# Button_PCBA.net
KiCad netlist of a schematic drawn in EAGLE
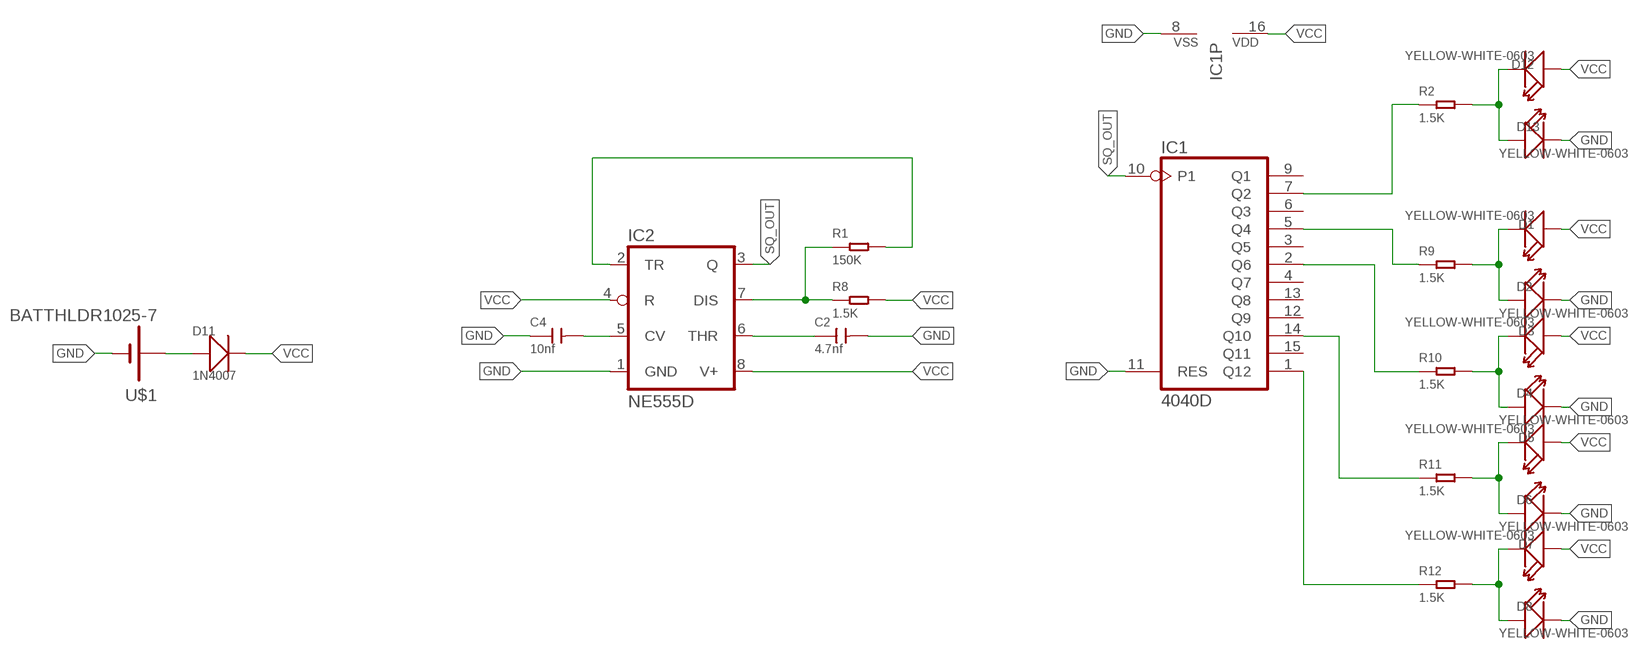
[diagram p0: schematic, sheet 1]

(export (version "E")
  (design (tool "Eeschema 10.0.6"))
  (components
    (comp (ref "C2")
      (value "4.7nf")
      (footprint "eagle-import:C0603")
      (fields (field (name "MPN") "CC0603KRX7R9BB472"))
      (libsource (lib "eagle-import") (part "CERAMIC-4.7NF-50V-10%-X7R(0603)"))
    )
    (comp (ref "C4")
      (value "10nf")
      (footprint "eagle-import:C0603")
      (fields (field (name "MPN") "CC0603KRX7R9BB103"))
      (libsource (lib "eagle-import") (part "CERAMIC-10NF-50V-10%-X7R(0603)"))
    )
    (comp (ref "D1")
      (value "YELLOW-WHITE-0603")
      (footprint "eagle-import:LED-0603")
      (fields (field (name "MPN") "ADL-0603W"))
      (libsource (lib "eagle-import") (part "SMD-LED-YELLOW-WHITE(0603)"))
    )
    (comp (ref "D2")
      (value "YELLOW-WHITE-0603")
      (footprint "eagle-import:LED-0603")
      (fields (field (name "MPN") "ADL-0603W"))
      (libsource (lib "eagle-import") (part "SMD-LED-YELLOW-WHITE(0603)"))
    )
    (comp (ref "D3")
      (value "YELLOW-WHITE-0603")
      (footprint "eagle-import:LED-0603")
      (fields (field (name "MPN") "ADL-0603W"))
      (libsource (lib "eagle-import") (part "SMD-LED-YELLOW-WHITE(0603)"))
    )
    (comp (ref "D4")
      (value "YELLOW-WHITE-0603")
      (footprint "eagle-import:LED-0603")
      (fields (field (name "MPN") "ADL-0603W"))
      (libsource (lib "eagle-import") (part "SMD-LED-YELLOW-WHITE(0603)"))
    )
    (comp (ref "D5")
      (value "YELLOW-WHITE-0603")
      (footprint "eagle-import:LED-0603")
      (fields (field (name "MPN") "ADL-0603W"))
      (libsource (lib "eagle-import") (part "SMD-LED-YELLOW-WHITE(0603)"))
    )
    (comp (ref "D6")
      (value "YELLOW-WHITE-0603")
      (footprint "eagle-import:LED-0603")
      (fields (field (name "MPN") "ADL-0603W"))
      (libsource (lib "eagle-import") (part "SMD-LED-YELLOW-WHITE(0603)"))
    )
    (comp (ref "D7")
      (value "YELLOW-WHITE-0603")
      (footprint "eagle-import:LED-0603")
      (fields (field (name "MPN") "ADL-0603W"))
      (libsource (lib "eagle-import") (part "SMD-LED-YELLOW-WHITE(0603)"))
    )
    (comp (ref "D8")
      (value "YELLOW-WHITE-0603")
      (footprint "eagle-import:LED-0603")
      (fields (field (name "MPN") "ADL-0603W"))
      (libsource (lib "eagle-import") (part "SMD-LED-YELLOW-WHITE(0603)"))
    )
    (comp (ref "D11")
      (value "1N4007")
      (footprint "eagle-import:DO-214AC")
      (libsource (lib "eagle-import") (part "DIODE-GEN-PURPOSE-1KV-1A(DO-214AC)"))
    )
    (comp (ref "D12")
      (value "YELLOW-WHITE-0603")
      (footprint "eagle-import:LED-0603")
      (fields (field (name "MPN") "ADL-0603W"))
      (libsource (lib "eagle-import") (part "SMD-LED-YELLOW-WHITE(0603)"))
    )
    (comp (ref "D13")
      (value "YELLOW-WHITE-0603")
      (footprint "eagle-import:LED-0603")
      (fields (field (name "MPN") "ADL-0603W"))
      (libsource (lib "eagle-import") (part "SMD-LED-YELLOW-WHITE(0603)"))
    )
    (comp (ref "IC1")
      (value "4040D")
      (footprint "eagle-import:SO16")
      (libsource (lib "eagle-import") (part "4040D"))
    )
    (comp (ref "IC2")
      (value "NE555D")
      (footprint "eagle-import:SO08")
      (libsource (lib "eagle-import") (part "555DNE"))
    )
    (comp (ref "R1")
      (value "150K")
      (footprint "eagle-import:R0603")
      (fields (field (name "MPN") "RC0603FR-07150KL"))
      (libsource (lib "eagle-import") (part "SMD-RES-150K-1%-1/10W(0603)"))
    )
    (comp (ref "R2")
      (value "1.5K")
      (footprint "eagle-import:R0603")
      (fields (field (name "MPN") "RC0603FR-071K5L"))
      (libsource (lib "eagle-import") (part "SMD-RES-680R-1%-1/10W(0603)"))
    )
    (comp (ref "R8")
      (value "1.5K")
      (footprint "eagle-import:R0603")
      (fields (field (name "MPN") "RC0603FR-071K5L"))
      (libsource (lib "eagle-import") (part "SMD-RES-4.7K-1%-1/10W(0603)"))
    )
    (comp (ref "R9")
      (value "1.5K")
      (footprint "eagle-import:R0603")
      (fields (field (name "MPN") "RC0603FR-071K5L"))
      (libsource (lib "eagle-import") (part "SMD-RES-680R-1%-1/10W(0603)"))
    )
    (comp (ref "R10")
      (value "1.5K")
      (footprint "eagle-import:R0603")
      (fields (field (name "MPN") "RC0603FR-071K5L"))
      (libsource (lib "eagle-import") (part "SMD-RES-680R-1%-1/10W(0603)"))
    )
    (comp (ref "R11")
      (value "1.5K")
      (footprint "eagle-import:R0603")
      (fields (field (name "MPN") "RC0603FR-071K5L"))
      (libsource (lib "eagle-import") (part "SMD-RES-680R-1%-1/10W(0603)"))
    )
    (comp (ref "R12")
      (value "1.5K")
      (footprint "eagle-import:R0603")
      (fields (field (name "MPN") "RC0603FR-071K5L"))
      (libsource (lib "eagle-import") (part "SMD-RES-680R-1%-1/10W(0603)"))
    )
    (comp (ref "U$1")
      (value "BATTHLDR1025-7")
      (footprint "eagle-import:BATTHLDR1025-7")
      (libsource (lib "eagle-import") (part "BATTHLDR1025-7"))
    )
  )
  (nets
    (net (code "1") (name "GND") (class "Default")
      (node (ref "C2") (pin "2") (pinfunction "2_2") (pintype "passive"))
      (node (ref "C4") (pin "1") (pinfunction "1_1") (pintype "passive"))
      (node (ref "D13") (pin "-") (pinfunction "-_-") (pintype "passive"))
      (node (ref "D2") (pin "-") (pinfunction "-_-") (pintype "passive"))
      (node (ref "D4") (pin "-") (pinfunction "-_-") (pintype "passive"))
      (node (ref "D6") (pin "-") (pinfunction "-_-") (pintype "passive"))
      (node (ref "D8") (pin "-") (pinfunction "-_-") (pintype "passive"))
      (node (ref "IC1") (pin "11") (pinfunction "RES_11") (pintype "input"))
      (node (ref "IC1") (pin "8") (pinfunction "VSS_8") (pintype "power_in"))
      (node (ref "IC2") (pin "1") (pinfunction "GND_1") (pintype "power_in"))
      (node (ref "U$1") (pin "NEGATIVE") (pinfunction "-_NEGATIVE") (pintype "power_in"))
    )
    (net (code "2") (name "Net-(D1-Pad-)") (class "Default")
      (node (ref "D1") (pin "-") (pinfunction "-_-") (pintype "passive"))
      (node (ref "D2") (pin "+") (pinfunction "+_+") (pintype "passive"))
      (node (ref "R9") (pin "2") (pinfunction "2_2") (pintype "passive"))
    )
    (net (code "3") (name "Net-(D3-Pad-)") (class "Default")
      (node (ref "D3") (pin "-") (pinfunction "-_-") (pintype "passive"))
      (node (ref "D4") (pin "+") (pinfunction "+_+") (pintype "passive"))
      (node (ref "R10") (pin "2") (pinfunction "2_2") (pintype "passive"))
    )
    (net (code "4") (name "Net-(D5-Pad-)") (class "Default")
      (node (ref "D5") (pin "-") (pinfunction "-_-") (pintype "passive"))
      (node (ref "D6") (pin "+") (pinfunction "+_+") (pintype "passive"))
      (node (ref "R11") (pin "2") (pinfunction "2_2") (pintype "passive"))
    )
    (net (code "5") (name "Net-(D7-Pad-)") (class "Default")
      (node (ref "D7") (pin "-") (pinfunction "-_-") (pintype "passive"))
      (node (ref "D8") (pin "+") (pinfunction "+_+") (pintype "passive"))
      (node (ref "R12") (pin "2") (pinfunction "2_2") (pintype "passive"))
    )
    (net (code "6") (name "Net-(D11-+)") (class "Default")
      (node (ref "D11") (pin "1") (pinfunction "+_1") (pintype "passive"))
      (node (ref "U$1") (pin "POSITIVE") (pinfunction "+_POSITIVE") (pintype "power_in"))
    )
    (net (code "7") (name "Net-(D12-Pad-)") (class "Default")
      (node (ref "D12") (pin "-") (pinfunction "-_-") (pintype "passive"))
      (node (ref "D13") (pin "+") (pinfunction "+_+") (pintype "passive"))
      (node (ref "R2") (pin "2") (pinfunction "2_2") (pintype "passive"))
    )
    (net (code "8") (name "Net-(IC1A-Q2)") (class "Default")
      (node (ref "IC1") (pin "7") (pinfunction "Q2_7") (pintype "output"))
      (node (ref "R2") (pin "1") (pinfunction "1_1") (pintype "passive"))
    )
    (net (code "9") (name "Net-(IC1A-Q4)") (class "Default")
      (node (ref "IC1") (pin "5") (pinfunction "Q4_5") (pintype "output"))
      (node (ref "R9") (pin "1") (pinfunction "1_1") (pintype "passive"))
    )
    (net (code "10") (name "Net-(IC1A-Q6)") (class "Default")
      (node (ref "IC1") (pin "2") (pinfunction "Q6_2") (pintype "output"))
      (node (ref "R10") (pin "1") (pinfunction "1_1") (pintype "passive"))
    )
    (net (code "11") (name "Net-(IC1A-Q10)") (class "Default")
      (node (ref "IC1") (pin "14") (pinfunction "Q10_14") (pintype "output"))
      (node (ref "R11") (pin "1") (pinfunction "1_1") (pintype "passive"))
    )
    (net (code "12") (name "Net-(IC1A-Q12)") (class "Default")
      (node (ref "IC1") (pin "1") (pinfunction "Q12_1") (pintype "output"))
      (node (ref "R12") (pin "1") (pinfunction "1_1") (pintype "passive"))
    )
    (net (code "13") (name "Net-(IC2-CV)") (class "Default")
      (node (ref "C4") (pin "2") (pinfunction "2_2") (pintype "passive"))
      (node (ref "IC2") (pin "5") (pinfunction "CV_5") (pintype "input"))
    )
    (net (code "14") (name "Net-(IC2-DIS)") (class "Default")
      (node (ref "IC2") (pin "7") (pinfunction "DIS_7") (pintype "input"))
      (node (ref "R1") (pin "1") (pinfunction "1_1") (pintype "passive"))
      (node (ref "R8") (pin "1") (pinfunction "1_1") (pintype "passive"))
    )
    (net (code "15") (name "Net-(IC2-THR)") (class "Default")
      (node (ref "C2") (pin "1") (pinfunction "1_1") (pintype "passive"))
      (node (ref "IC2") (pin "6") (pinfunction "THR_6") (pintype "input"))
    )
    (net (code "16") (name "Net-(IC2-TR)") (class "Default")
      (node (ref "IC2") (pin "2") (pinfunction "TR_2") (pintype "input"))
      (node (ref "R1") (pin "2") (pinfunction "2_2") (pintype "passive"))
    )
    (net (code "17") (name "SQ_OUT") (class "Default")
      (node (ref "IC1") (pin "10") (pinfunction "P1_10") (pintype "input"))
      (node (ref "IC2") (pin "3") (pinfunction "Q_3") (pintype "output"))
    )
    (net (code "18") (name "VCC") (class "Default")
      (node (ref "D1") (pin "+") (pinfunction "+_+") (pintype "passive"))
      (node (ref "D11") (pin "2") (pinfunction "-_2") (pintype "passive"))
      (node (ref "D12") (pin "+") (pinfunction "+_+") (pintype "passive"))
      (node (ref "D3") (pin "+") (pinfunction "+_+") (pintype "passive"))
      (node (ref "D5") (pin "+") (pinfunction "+_+") (pintype "passive"))
      (node (ref "D7") (pin "+") (pinfunction "+_+") (pintype "passive"))
      (node (ref "IC1") (pin "16") (pinfunction "VDD_16") (pintype "power_in"))
      (node (ref "IC2") (pin "4") (pinfunction "R_4") (pintype "input"))
      (node (ref "IC2") (pin "8") (pinfunction "V+_8") (pintype "power_in"))
      (node (ref "R8") (pin "2") (pinfunction "2_2") (pintype "passive"))
    )
    (net (code "19") (name "unconnected-(IC1A-Q1-Pad9)") (class "Default")
      (node (ref "IC1") (pin "9") (pinfunction "Q1_9") (pintype "output"))
    )
    (net (code "20") (name "unconnected-(IC1A-Q3-Pad6)") (class "Default")
      (node (ref "IC1") (pin "6") (pinfunction "Q3_6") (pintype "output"))
    )
    (net (code "21") (name "unconnected-(IC1A-Q5-Pad3)") (class "Default")
      (node (ref "IC1") (pin "3") (pinfunction "Q5_3") (pintype "output"))
    )
    (net (code "22") (name "unconnected-(IC1A-Q7-Pad4)") (class "Default")
      (node (ref "IC1") (pin "4") (pinfunction "Q7_4") (pintype "output"))
    )
    (net (code "23") (name "unconnected-(IC1A-Q8-Pad13)") (class "Default")
      (node (ref "IC1") (pin "13") (pinfunction "Q8_13") (pintype "output"))
    )
    (net (code "24") (name "unconnected-(IC1A-Q9-Pad12)") (class "Default")
      (node (ref "IC1") (pin "12") (pinfunction "Q9_12") (pintype "output"))
    )
    (net (code "25") (name "unconnected-(IC1A-Q11-Pad15)") (class "Default")
      (node (ref "IC1") (pin "15") (pinfunction "Q11_15") (pintype "output"))
    )
  )
)
